# OvenController.net
KiCad netlist of a schematic drawn in EAGLE
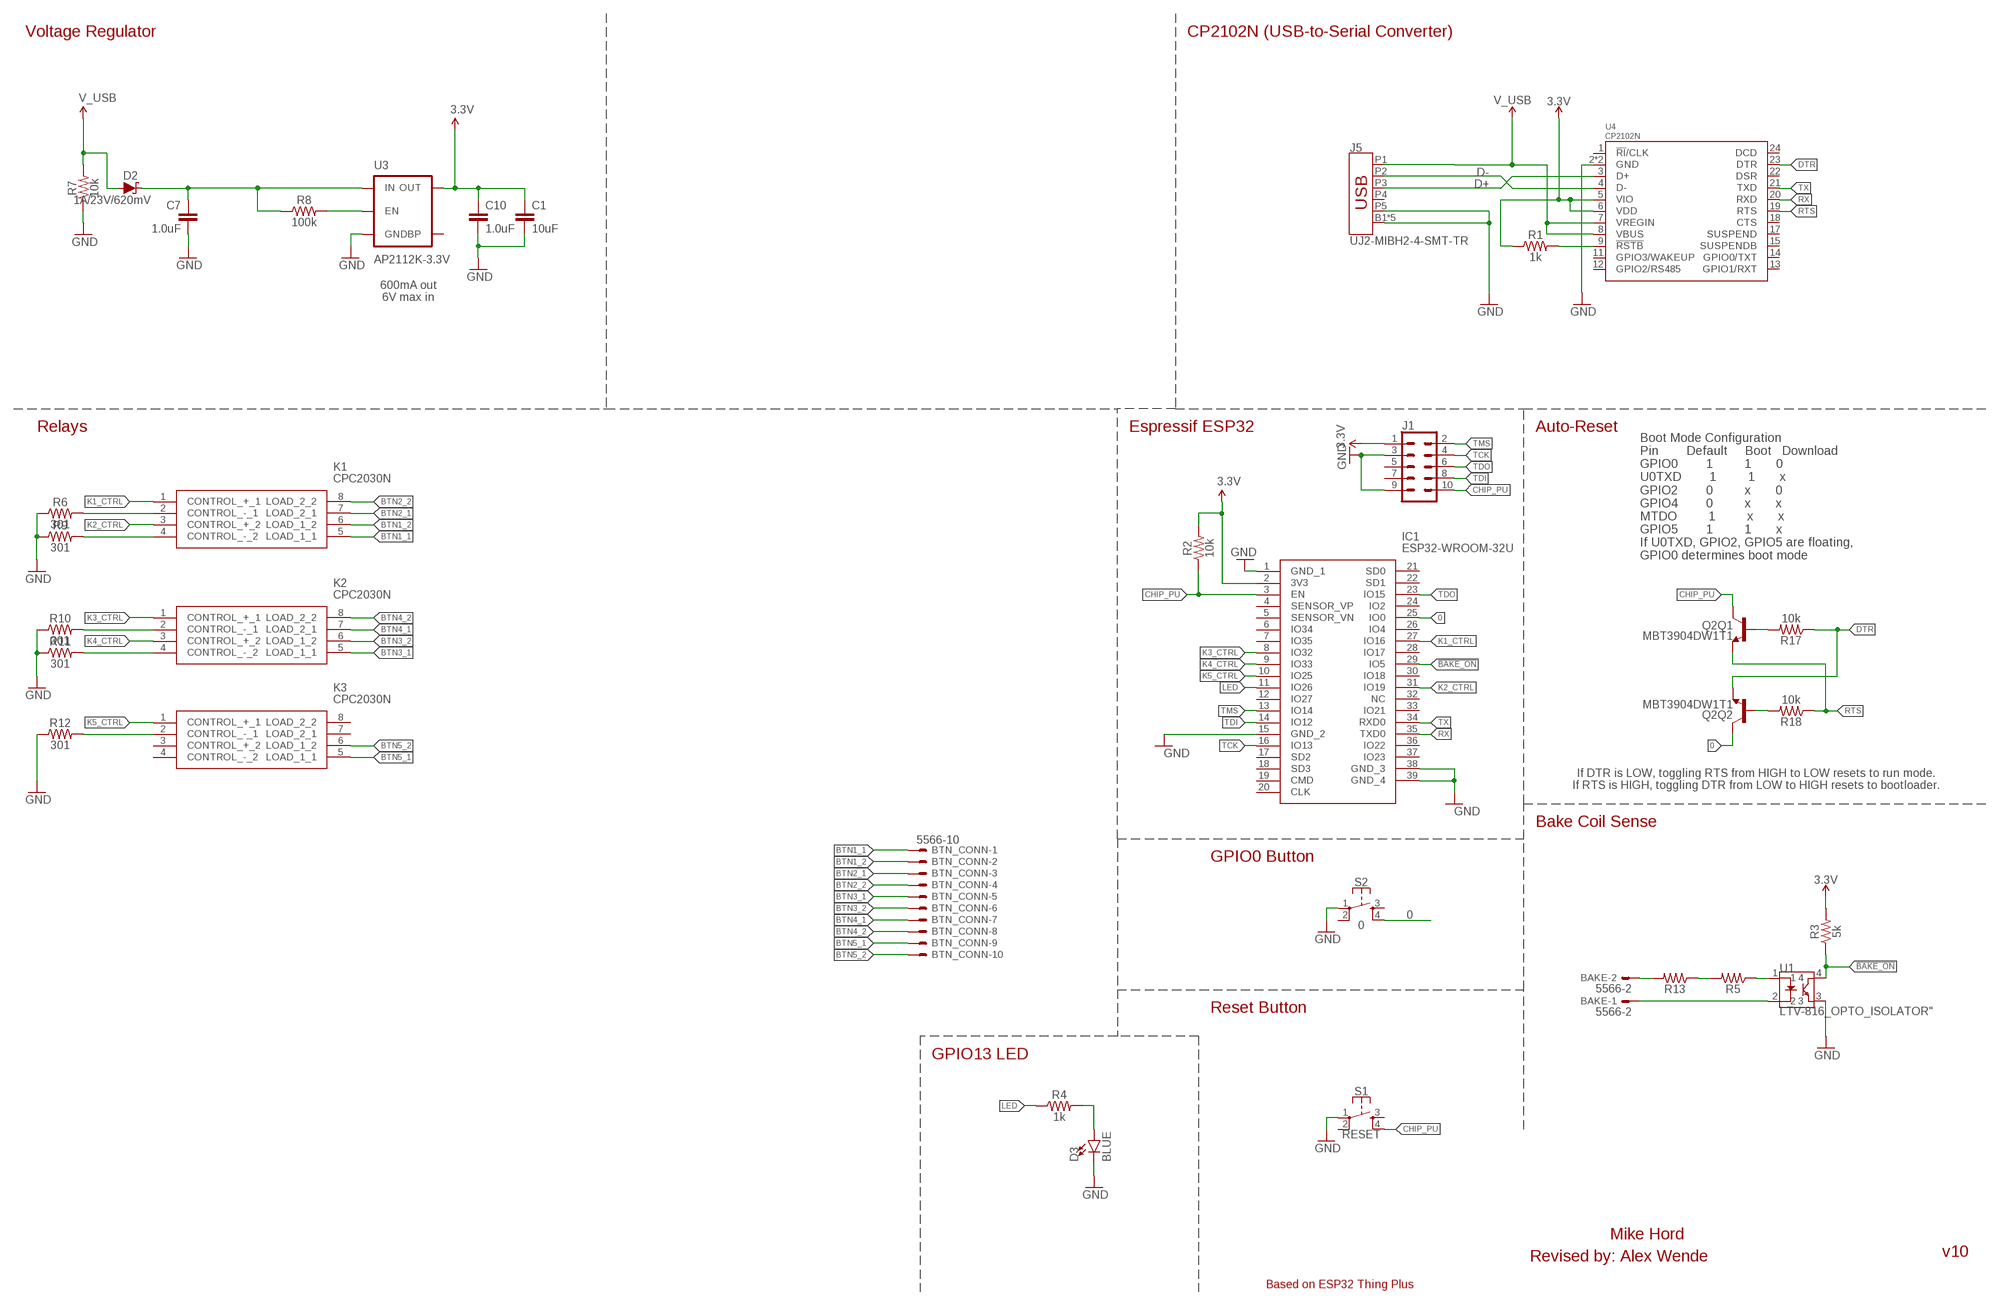
[diagram p0: schematic, sheet 1]

(export (version "E")
  (design (tool "Eeschema 10.0.6"))
  (components
    (comp (ref "BAKE")
      (value "5566-2")
      (footprint "eagle-import:5566-2")
      (fields (field (name "MF") "MOLEX"))
      (libsource (lib "eagle-import") (part "5566-2"))
    )
    (comp (ref "BTN_CONN")
      (value "5566-10")
      (footprint "eagle-import:5566-10")
      (fields (field (name "MF") "MOLEX"))
      (libsource (lib "eagle-import") (part "5566-10"))
    )
    (comp (ref "C1")
      (value "10uF")
      (footprint "eagle-import:0603")
      (libsource (lib "eagle-import") (part "10UF-0603-6.3V-20%"))
    )
    (comp (ref "C7")
      (value "1.0uF")
      (footprint "eagle-import:0603")
      (libsource (lib "eagle-import") (part "1.0UF-0603-16V-10%-X7R"))
    )
    (comp (ref "C10")
      (value "1.0uF")
      (footprint "eagle-import:0603")
      (libsource (lib "eagle-import") (part "1.0UF-0603-16V-10%-X7R"))
    )
    (comp (ref "D2")
      (value "1A/23V/620mV")
      (footprint "eagle-import:SOD-323")
      (libsource (lib "eagle-import") (part "DIODE-SCHOTTKY-BAT20J"))
    )
    (comp (ref "D3")
      (value "BLUE")
      (footprint "eagle-import:LED-0603")
      (libsource (lib "eagle-import") (part "LED-BLUE0603"))
    )
    (comp (ref "IC1")
      (value "ESP32-WROOM-32U")
      (footprint "eagle-import:ESP32WROOM32D")
      (fields (field (name "MOUSER_PART_NUMBER") "356-ESP32-WROOM-32U"))
      (libsource (lib "eagle-import") (part "ESP32-WROOM-32U"))
    )
    (comp (ref "J1")
      (value "CONN_05X2PTH")
      (footprint "eagle-import:2X5")
      (libsource (lib "eagle-import") (part "CONN_05X2PTH"))
    )
    (comp (ref "J5")
      (value "UJ2-MIBH2-4-SMT-TR")
      (footprint "eagle-import:UJ2-MIBH2-4-SMT-TR")
      (fields (field (name "MFR") "CUI"))
      (libsource (lib "eagle-import") (part "UJ2-MIBH2-4-SMT-TR"))
    )
    (comp (ref "K1")
      (value "CPC2030N")
      (footprint "eagle-import:SOP254P610X218-8N")
      (fields (field (name "MOUSER_PART_NUMBER") "849-CPC2030N"))
      (libsource (lib "eagle-import") (part "CPC2030N"))
    )
    (comp (ref "K2")
      (value "CPC2030N")
      (footprint "eagle-import:SOP254P610X218-8N")
      (fields (field (name "MOUSER_PART_NUMBER") "849-CPC2030N"))
      (libsource (lib "eagle-import") (part "CPC2030N"))
    )
    (comp (ref "K3")
      (value "CPC2030N")
      (footprint "eagle-import:SOP254P610X218-8N")
      (fields (field (name "MOUSER_PART_NUMBER") "849-CPC2030N"))
      (libsource (lib "eagle-import") (part "CPC2030N"))
    )
    (comp (ref "Q2")
      (value "MBT3904DW1T1")
      (footprint "eagle-import:SC70-6")
      (libsource (lib "eagle-import") (part "TRANS_NPN_DUAL-MBT3904DW1T1"))
    )
    (comp (ref "R1")
      (value "1k")
      (footprint "eagle-import:0603")
      (libsource (lib "eagle-import") (part "1KOHM-0603-1/10W-1%"))
    )
    (comp (ref "R2")
      (value "10k")
      (footprint "eagle-import:0603")
      (libsource (lib "eagle-import") (part "10KOHM-0603-1/10W-1%"))
    )
    (comp (ref "R3")
      (value "5k")
      (footprint "eagle-import:0603")
      (libsource (lib "eagle-import") (part "RESISTOR0603"))
    )
    (comp (ref "R4")
      (value "1k")
      (footprint "eagle-import:0603")
      (libsource (lib "eagle-import") (part "1KOHM-0603-1/10W-1%"))
    )
    (comp (ref "R5")
      (value "300")
      (footprint "eagle-import:R1210W")
      (libsource (lib "eagle-import") (part "R-US_R1210W"))
    )
    (comp (ref "R6")
      (value "301")
      (footprint "eagle-import:0603")
      (libsource (lib "eagle-import") (part "RESISTOR0603"))
    )
    (comp (ref "R7")
      (value "10k")
      (footprint "eagle-import:0603")
      (libsource (lib "eagle-import") (part "10KOHM-0603-1/10W-1%"))
    )
    (comp (ref "R8")
      (value "100k")
      (footprint "eagle-import:0603")
      (libsource (lib "eagle-import") (part "100KOHM-0603-1/10W-1%"))
    )
    (comp (ref "R9")
      (value "301")
      (footprint "eagle-import:0603")
      (libsource (lib "eagle-import") (part "RESISTOR0603"))
    )
    (comp (ref "R10")
      (value "301")
      (footprint "eagle-import:0603")
      (libsource (lib "eagle-import") (part "RESISTOR0603"))
    )
    (comp (ref "R11")
      (value "301")
      (footprint "eagle-import:0603")
      (libsource (lib "eagle-import") (part "RESISTOR0603"))
    )
    (comp (ref "R12")
      (value "301")
      (footprint "eagle-import:0603")
      (libsource (lib "eagle-import") (part "RESISTOR0603"))
    )
    (comp (ref "R13")
      (value "300")
      (footprint "eagle-import:R1210W")
      (libsource (lib "eagle-import") (part "R-US_R1210W"))
    )
    (comp (ref "R17")
      (value "10k")
      (footprint "eagle-import:0603")
      (libsource (lib "eagle-import") (part "10KOHM-0603-1/10W-1%"))
    )
    (comp (ref "R18")
      (value "10k")
      (footprint "eagle-import:0603")
      (libsource (lib "eagle-import") (part "10KOHM-0603-1/10W-1%"))
    )
    (comp (ref "S1")
      (value "RESET")
      (footprint "eagle-import:TACTILE_SWITCH_SMD_4.6X2.8MM")
      (libsource (lib "eagle-import") (part "MOMENTARY-SWITCH-SPST-2-SMD-4.6X2.8MM"))
    )
    (comp (ref "S2")
      (value "0")
      (footprint "eagle-import:TACTILE_SWITCH_SMD_4.6X2.8MM")
      (libsource (lib "eagle-import") (part "MOMENTARY-SWITCH-SPST-2-SMD-4.6X2.8MM"))
    )
    (comp (ref "U1")
      (value "LTV-816_OPTO_ISOLATOR\"")
      (footprint "eagle-import:LTV-816_4PIN_DIP")
      (libsource (lib "eagle-import") (part "LTV-816_OPTO_ISOLATOR{dblquote}"))
    )
    (comp (ref "U3")
      (value "AP2112K-3.3V")
      (footprint "eagle-import:SOT23-5")
      (libsource (lib "eagle-import") (part "V_REG_LDOSMD"))
    )
    (comp (ref "U4")
      (value "CP2102N")
      (footprint "eagle-import:QFN24")
      (libsource (lib "eagle-import") (part "CP2102N"))
    )
  )
  (nets
    (net (code "1") (name "/CONTROL_+_2") (class "Default")
      (node (ref "K3") (pin "3") (pinfunction "CONTROL_+_2_3") (pintype "power_in"))
    )
    (net (code "2") (name "/CONTROL_-_2") (class "Default")
      (node (ref "K3") (pin "4") (pinfunction "CONTROL_-_2_4") (pintype "power_in"))
    )
    (net (code "3") (name "/D+") (class "Default")
      (node (ref "J5") (pin "P3") (pinfunction "D+_P3") (pintype "bidirectional"))
      (node (ref "U4") (pin "3") (pinfunction "D+_3") (pintype "bidirectional"))
    )
    (net (code "4") (name "/D-") (class "Default")
      (node (ref "J5") (pin "P2") (pinfunction "D-_P2") (pintype "bidirectional"))
      (node (ref "U4") (pin "4") (pinfunction "D-_4") (pintype "bidirectional"))
    )
    (net (code "5") (name "/~{BAKE_ON}") (class "Default")
      (node (ref "IC1") (pin "29") (pinfunction "IO5_29") (pintype "bidirectional"))
      (node (ref "R3") (pin "1") (pinfunction "1_1") (pintype "passive"))
      (node (ref "U1") (pin "4") (pinfunction "4_4") (pintype "bidirectional"))
    )
    (net (code "6") (name "0") (class "Default")
      (node (ref "IC1") (pin "25") (pinfunction "IO0_25") (pintype "bidirectional"))
      (node (ref "Q2") (pin "6") (pinfunction "C_6") (pintype "passive"))
      (node (ref "S2") (pin "4") (pinfunction "4_4") (pintype "passive"))
    )
    (net (code "7") (name "3.3V") (class "Default")
      (node (ref "C1") (pin "1") (pinfunction "1_1") (pintype "passive"))
      (node (ref "C10") (pin "1") (pinfunction "1_1") (pintype "passive"))
      (node (ref "IC1") (pin "2") (pinfunction "3V3_2") (pintype "bidirectional"))
      (node (ref "J1") (pin "1") (pinfunction "1_1") (pintype "passive"))
      (node (ref "R1") (pin "1") (pinfunction "1_1") (pintype "passive"))
      (node (ref "R2") (pin "2") (pinfunction "2_2") (pintype "passive"))
      (node (ref "R3") (pin "2") (pinfunction "2_2") (pintype "passive"))
      (node (ref "U3") (pin "5") (pinfunction "OUT_5") (pintype "passive"))
      (node (ref "U4") (pin "5") (pinfunction "VIO_5") (pintype "bidirectional"))
      (node (ref "U4") (pin "6") (pinfunction "VDD_6") (pintype "bidirectional"))
    )
    (net (code "8") (name "BTN1_1") (class "Default")
      (node (ref "BTN_CONN") (pin "1") (pinfunction "S_1") (pintype "passive"))
      (node (ref "K1") (pin "5") (pinfunction "LOAD_1_1_5") (pintype "bidirectional"))
    )
    (net (code "9") (name "BTN1_2") (class "Default")
      (node (ref "BTN_CONN") (pin "2") (pinfunction "S_2") (pintype "passive"))
      (node (ref "K1") (pin "6") (pinfunction "LOAD_1_2_6") (pintype "bidirectional"))
    )
    (net (code "10") (name "BTN2_1") (class "Default")
      (node (ref "BTN_CONN") (pin "3") (pinfunction "S_3") (pintype "passive"))
      (node (ref "K1") (pin "7") (pinfunction "LOAD_2_1_7") (pintype "bidirectional"))
    )
    (net (code "11") (name "BTN2_2") (class "Default")
      (node (ref "BTN_CONN") (pin "4") (pinfunction "S_4") (pintype "passive"))
      (node (ref "K1") (pin "8") (pinfunction "LOAD_2_2_8") (pintype "bidirectional"))
    )
    (net (code "12") (name "BTN3_1") (class "Default")
      (node (ref "BTN_CONN") (pin "5") (pinfunction "S_5") (pintype "passive"))
      (node (ref "K2") (pin "5") (pinfunction "LOAD_1_1_5") (pintype "bidirectional"))
    )
    (net (code "13") (name "BTN3_2") (class "Default")
      (node (ref "BTN_CONN") (pin "6") (pinfunction "S_6") (pintype "passive"))
      (node (ref "K2") (pin "6") (pinfunction "LOAD_1_2_6") (pintype "bidirectional"))
    )
    (net (code "14") (name "BTN4_1") (class "Default")
      (node (ref "BTN_CONN") (pin "7") (pinfunction "S_7") (pintype "passive"))
      (node (ref "K2") (pin "7") (pinfunction "LOAD_2_1_7") (pintype "bidirectional"))
    )
    (net (code "15") (name "BTN4_2") (class "Default")
      (node (ref "BTN_CONN") (pin "8") (pinfunction "S_8") (pintype "passive"))
      (node (ref "K2") (pin "8") (pinfunction "LOAD_2_2_8") (pintype "bidirectional"))
    )
    (net (code "16") (name "BTN5_1") (class "Default")
      (node (ref "BTN_CONN") (pin "9") (pinfunction "S_9") (pintype "passive"))
      (node (ref "K3") (pin "5") (pinfunction "LOAD_1_1_5") (pintype "bidirectional"))
    )
    (net (code "17") (name "BTN5_2") (class "Default")
      (node (ref "BTN_CONN") (pin "10") (pinfunction "S_10") (pintype "passive"))
      (node (ref "K3") (pin "6") (pinfunction "LOAD_1_2_6") (pintype "bidirectional"))
    )
    (net (code "18") (name "CHIP_PU") (class "Default")
      (node (ref "IC1") (pin "3") (pinfunction "EN_3") (pintype "bidirectional"))
      (node (ref "J1") (pin "10") (pinfunction "10_10") (pintype "passive"))
      (node (ref "Q2") (pin "3") (pinfunction "C_3") (pintype "passive"))
      (node (ref "R2") (pin "1") (pinfunction "1_1") (pintype "passive"))
      (node (ref "S1") (pin "4") (pinfunction "4_4") (pintype "passive"))
    )
    (net (code "19") (name "DTR") (class "Default")
      (node (ref "Q2") (pin "1") (pinfunction "E_1") (pintype "passive"))
      (node (ref "R17") (pin "1") (pinfunction "1_1") (pintype "passive"))
      (node (ref "U4") (pin "23") (pinfunction "DTR_23") (pintype "bidirectional"))
    )
    (net (code "20") (name "GND") (class "Default")
      (node (ref "C1") (pin "2") (pinfunction "2_2") (pintype "passive"))
      (node (ref "C10") (pin "2") (pinfunction "2_2") (pintype "passive"))
      (node (ref "C7") (pin "2") (pinfunction "2_2") (pintype "passive"))
      (node (ref "D3") (pin "C") (pinfunction "C_C") (pintype "passive"))
      (node (ref "IC1") (pin "1") (pinfunction "GND_1_1") (pintype "bidirectional"))
      (node (ref "IC1") (pin "15") (pinfunction "GND_2_15") (pintype "bidirectional"))
      (node (ref "IC1") (pin "38") (pinfunction "GND_3_38") (pintype "bidirectional"))
      (node (ref "IC1") (pin "39") (pinfunction "GND_4_39") (pintype "bidirectional"))
      (node (ref "J1") (pin "3") (pinfunction "3_3") (pintype "passive"))
      (node (ref "J1") (pin "9") (pinfunction "9_9") (pintype "passive"))
      (node (ref "J5") (pin "B1") (pinfunction "SHIELD_B1") (pintype "bidirectional"))
      (node (ref "J5") (pin "B2") (pinfunction "SHIELD_B2") (pintype "bidirectional"))
      (node (ref "J5") (pin "B3") (pinfunction "SHIELD_B3") (pintype "bidirectional"))
      (node (ref "J5") (pin "B4") (pinfunction "SHIELD_B4") (pintype "bidirectional"))
      (node (ref "J5") (pin "B5") (pinfunction "SHIELD_B5") (pintype "bidirectional"))
      (node (ref "J5") (pin "P5") (pinfunction "GND_P5") (pintype "power_in"))
      (node (ref "R10") (pin "1") (pinfunction "1_1") (pintype "passive"))
      (node (ref "R11") (pin "1") (pinfunction "1_1") (pintype "passive"))
      (node (ref "R12") (pin "1") (pinfunction "1_1") (pintype "passive"))
      (node (ref "R6") (pin "1") (pinfunction "1_1") (pintype "passive"))
      (node (ref "R7") (pin "1") (pinfunction "1_1") (pintype "passive"))
      (node (ref "R9") (pin "1") (pinfunction "1_1") (pintype "passive"))
      (node (ref "S1") (pin "1") (pinfunction "1_1") (pintype "passive"))
      (node (ref "S2") (pin "1") (pinfunction "1_1") (pintype "passive"))
      (node (ref "U1") (pin "3") (pinfunction "3_3") (pintype "bidirectional"))
      (node (ref "U3") (pin "2") (pinfunction "GND_2") (pintype "input"))
      (node (ref "U4") (pin "2") (pinfunction "GND_2") (pintype "bidirectional"))
      (node (ref "U4") (pin "PAD") (pinfunction "GND_PAD") (pintype "bidirectional"))
    )
    (net (code "21") (name "K1_CTRL") (class "Default")
      (node (ref "IC1") (pin "27") (pinfunction "IO16_27") (pintype "bidirectional"))
      (node (ref "K1") (pin "1") (pinfunction "CONTROL_+_1_1") (pintype "power_in"))
    )
    (net (code "22") (name "K2_CTRL") (class "Default")
      (node (ref "IC1") (pin "31") (pinfunction "IO19_31") (pintype "bidirectional"))
      (node (ref "K1") (pin "3") (pinfunction "CONTROL_+_2_3") (pintype "power_in"))
    )
    (net (code "23") (name "K3_CTRL") (class "Default")
      (node (ref "IC1") (pin "8") (pinfunction "IO32_8") (pintype "bidirectional"))
      (node (ref "K2") (pin "1") (pinfunction "CONTROL_+_1_1") (pintype "power_in"))
    )
    (net (code "24") (name "K4_CTRL") (class "Default")
      (node (ref "IC1") (pin "9") (pinfunction "IO33_9") (pintype "bidirectional"))
      (node (ref "K2") (pin "3") (pinfunction "CONTROL_+_2_3") (pintype "power_in"))
    )
    (net (code "25") (name "K5_CTRL") (class "Default")
      (node (ref "IC1") (pin "10") (pinfunction "IO25_10") (pintype "bidirectional"))
      (node (ref "K3") (pin "1") (pinfunction "CONTROL_+_1_1") (pintype "power_in"))
    )
    (net (code "26") (name "LED") (class "Default")
      (node (ref "IC1") (pin "11") (pinfunction "IO26_11") (pintype "bidirectional"))
      (node (ref "R4") (pin "1") (pinfunction "1_1") (pintype "passive"))
    )
    (net (code "27") (name "Net-(BAKEA-S)") (class "Default")
      (node (ref "BAKE") (pin "1") (pinfunction "S_1") (pintype "passive"))
      (node (ref "U1") (pin "2") (pinfunction "2_2") (pintype "bidirectional"))
    )
    (net (code "28") (name "Net-(BAKEB-S)") (class "Default")
      (node (ref "BAKE") (pin "2") (pinfunction "S_2") (pintype "passive"))
      (node (ref "R13") (pin "2") (pinfunction "2_2") (pintype "passive"))
    )
    (net (code "29") (name "Net-(D3-PadA)") (class "Default")
      (node (ref "D3") (pin "A") (pinfunction "A_A") (pintype "passive"))
      (node (ref "R4") (pin "2") (pinfunction "2_2") (pintype "passive"))
    )
    (net (code "30") (name "Net-(K1-CONTROL_-_1)") (class "Default")
      (node (ref "K1") (pin "2") (pinfunction "CONTROL_-_1_2") (pintype "power_in"))
      (node (ref "R6") (pin "2") (pinfunction "2_2") (pintype "passive"))
    )
    (net (code "31") (name "Net-(K1-CONTROL_-_2)") (class "Default")
      (node (ref "K1") (pin "4") (pinfunction "CONTROL_-_2_4") (pintype "power_in"))
      (node (ref "R9") (pin "2") (pinfunction "2_2") (pintype "passive"))
    )
    (net (code "32") (name "Net-(K2-CONTROL_-_1)") (class "Default")
      (node (ref "K2") (pin "2") (pinfunction "CONTROL_-_1_2") (pintype "power_in"))
      (node (ref "R10") (pin "2") (pinfunction "2_2") (pintype "passive"))
    )
    (net (code "33") (name "Net-(K2-CONTROL_-_2)") (class "Default")
      (node (ref "K2") (pin "4") (pinfunction "CONTROL_-_2_4") (pintype "power_in"))
      (node (ref "R11") (pin "2") (pinfunction "2_2") (pintype "passive"))
    )
    (net (code "34") (name "Net-(K3-CONTROL_-_1)") (class "Default")
      (node (ref "K3") (pin "2") (pinfunction "CONTROL_-_1_2") (pintype "power_in"))
      (node (ref "R12") (pin "2") (pinfunction "2_2") (pintype "passive"))
    )
    (net (code "35") (name "Net-(Q2A-B)") (class "Default")
      (node (ref "Q2") (pin "5") (pinfunction "B_5") (pintype "passive"))
      (node (ref "R17") (pin "2") (pinfunction "2_2") (pintype "passive"))
    )
    (net (code "36") (name "Net-(Q2B-B)") (class "Default")
      (node (ref "Q2") (pin "2") (pinfunction "B_2") (pintype "passive"))
      (node (ref "R18") (pin "2") (pinfunction "2_2") (pintype "passive"))
    )
    (net (code "37") (name "Net-(R5-Pad1)") (class "Default")
      (node (ref "R5") (pin "1") (pinfunction "1_1") (pintype "passive"))
      (node (ref "U1") (pin "1") (pinfunction "1_1") (pintype "bidirectional"))
    )
    (net (code "38") (name "Net-(R13-Pad1)") (class "Default")
      (node (ref "R13") (pin "1") (pinfunction "1_1") (pintype "passive"))
      (node (ref "R5") (pin "2") (pinfunction "2_2") (pintype "passive"))
    )
    (net (code "39") (name "Net-(U3-EN)") (class "Default")
      (node (ref "R8") (pin "2") (pinfunction "2_2") (pintype "passive"))
      (node (ref "U3") (pin "3") (pinfunction "EN_3") (pintype "input"))
    )
    (net (code "40") (name "Net-(U3-IN)") (class "Default")
      (node (ref "C7") (pin "1") (pinfunction "1_1") (pintype "passive"))
      (node (ref "D2") (pin "C") (pinfunction "C_C") (pintype "passive"))
      (node (ref "R8") (pin "1") (pinfunction "1_1") (pintype "passive"))
      (node (ref "U3") (pin "1") (pinfunction "IN_1") (pintype "input"))
    )
    (net (code "41") (name "Net-(U4-~{RSTB})") (class "Default")
      (node (ref "R1") (pin "2") (pinfunction "2_2") (pintype "passive"))
      (node (ref "U4") (pin "9") (pinfunction "~{RSTB}_9") (pintype "bidirectional"))
    )
    (net (code "42") (name "RTS") (class "Default")
      (node (ref "Q2") (pin "4") (pinfunction "E_4") (pintype "passive"))
      (node (ref "R18") (pin "1") (pinfunction "1_1") (pintype "passive"))
      (node (ref "U4") (pin "19") (pinfunction "RTS_19") (pintype "bidirectional"))
    )
    (net (code "43") (name "RX") (class "Default")
      (node (ref "IC1") (pin "35") (pinfunction "TXD0_35") (pintype "bidirectional"))
      (node (ref "U4") (pin "20") (pinfunction "RXD_20") (pintype "bidirectional"))
    )
    (net (code "44") (name "TCK") (class "Default")
      (node (ref "IC1") (pin "16") (pinfunction "IO13_16") (pintype "bidirectional"))
      (node (ref "J1") (pin "4") (pinfunction "4_4") (pintype "passive"))
    )
    (net (code "45") (name "TDI") (class "Default")
      (node (ref "IC1") (pin "14") (pinfunction "IO12_14") (pintype "bidirectional"))
      (node (ref "J1") (pin "8") (pinfunction "8_8") (pintype "passive"))
    )
    (net (code "46") (name "TDO") (class "Default")
      (node (ref "IC1") (pin "23") (pinfunction "IO15_23") (pintype "bidirectional"))
      (node (ref "J1") (pin "6") (pinfunction "6_6") (pintype "passive"))
    )
    (net (code "47") (name "TMS") (class "Default")
      (node (ref "IC1") (pin "13") (pinfunction "IO14_13") (pintype "bidirectional"))
      (node (ref "J1") (pin "2") (pinfunction "2_2") (pintype "passive"))
    )
    (net (code "48") (name "TX") (class "Default")
      (node (ref "IC1") (pin "34") (pinfunction "RXD0_34") (pintype "bidirectional"))
      (node (ref "U4") (pin "21") (pinfunction "TXD_21") (pintype "bidirectional"))
    )
    (net (code "49") (name "V_USB") (class "Default")
      (node (ref "D2") (pin "A") (pinfunction "A_A") (pintype "passive"))
      (node (ref "J5") (pin "P1") (pinfunction "VBUS_P1") (pintype "power_in"))
      (node (ref "R7") (pin "2") (pinfunction "2_2") (pintype "passive"))
      (node (ref "U4") (pin "7") (pinfunction "VREGIN_7") (pintype "bidirectional"))
      (node (ref "U4") (pin "8") (pinfunction "VBUS_8") (pintype "bidirectional"))
    )
    (net (code "50") (name "unconnected-(IC1-CLK-Pad20)") (class "Default")
      (node (ref "IC1") (pin "20") (pinfunction "CLK_20") (pintype "bidirectional"))
    )
    (net (code "51") (name "unconnected-(IC1-CMD-Pad19)") (class "Default")
      (node (ref "IC1") (pin "19") (pinfunction "CMD_19") (pintype "bidirectional"))
    )
    (net (code "52") (name "unconnected-(IC1-IO2-Pad24)") (class "Default")
      (node (ref "IC1") (pin "24") (pinfunction "IO2_24") (pintype "bidirectional"))
    )
    (net (code "53") (name "unconnected-(IC1-IO4-Pad26)") (class "Default")
      (node (ref "IC1") (pin "26") (pinfunction "IO4_26") (pintype "bidirectional"))
    )
    (net (code "54") (name "unconnected-(IC1-IO17-Pad28)") (class "Default")
      (node (ref "IC1") (pin "28") (pinfunction "IO17_28") (pintype "bidirectional"))
    )
    (net (code "55") (name "unconnected-(IC1-IO18-Pad30)") (class "Default")
      (node (ref "IC1") (pin "30") (pinfunction "IO18_30") (pintype "bidirectional"))
    )
    (net (code "56") (name "unconnected-(IC1-IO21-Pad33)") (class "Default")
      (node (ref "IC1") (pin "33") (pinfunction "IO21_33") (pintype "bidirectional"))
    )
    (net (code "57") (name "unconnected-(IC1-IO22-Pad36)") (class "Default")
      (node (ref "IC1") (pin "36") (pinfunction "IO22_36") (pintype "bidirectional"))
    )
    (net (code "58") (name "unconnected-(IC1-IO23-Pad37)") (class "Default")
      (node (ref "IC1") (pin "37") (pinfunction "IO23_37") (pintype "bidirectional"))
    )
    (net (code "59") (name "unconnected-(IC1-IO27-Pad12)") (class "Default")
      (node (ref "IC1") (pin "12") (pinfunction "IO27_12") (pintype "bidirectional"))
    )
    (net (code "60") (name "unconnected-(IC1-IO34-Pad6)") (class "Default")
      (node (ref "IC1") (pin "6") (pinfunction "IO34_6") (pintype "bidirectional"))
    )
    (net (code "61") (name "unconnected-(IC1-IO35-Pad7)") (class "Default")
      (node (ref "IC1") (pin "7") (pinfunction "IO35_7") (pintype "bidirectional"))
    )
    (net (code "62") (name "unconnected-(IC1-NC-Pad32)") (class "Default")
      (node (ref "IC1") (pin "32") (pinfunction "NC_32") (pintype "no_connect"))
    )
    (net (code "63") (name "unconnected-(IC1-SD0-Pad21)") (class "Default")
      (node (ref "IC1") (pin "21") (pinfunction "SD0_21") (pintype "bidirectional"))
    )
    (net (code "64") (name "unconnected-(IC1-SD1-Pad22)") (class "Default")
      (node (ref "IC1") (pin "22") (pinfunction "SD1_22") (pintype "bidirectional"))
    )
    (net (code "65") (name "unconnected-(IC1-SD2-Pad17)") (class "Default")
      (node (ref "IC1") (pin "17") (pinfunction "SD2_17") (pintype "bidirectional"))
    )
    (net (code "66") (name "unconnected-(IC1-SD3-Pad18)") (class "Default")
      (node (ref "IC1") (pin "18") (pinfunction "SD3_18") (pintype "bidirectional"))
    )
    (net (code "67") (name "unconnected-(IC1-SENSOR_VN-Pad5)") (class "Default")
      (node (ref "IC1") (pin "5") (pinfunction "SENSOR_VN_5") (pintype "bidirectional"))
    )
    (net (code "68") (name "unconnected-(IC1-SENSOR_VP-Pad4)") (class "Default")
      (node (ref "IC1") (pin "4") (pinfunction "SENSOR_VP_4") (pintype "bidirectional"))
    )
    (net (code "69") (name "unconnected-(J1-Pad5)") (class "Default")
      (node (ref "J1") (pin "5") (pinfunction "5_5") (pintype "passive"))
    )
    (net (code "70") (name "unconnected-(J1-Pad7)") (class "Default")
      (node (ref "J1") (pin "7") (pinfunction "7_7") (pintype "passive"))
    )
    (net (code "71") (name "unconnected-(J5-ID-PadP4)") (class "Default")
      (node (ref "J5") (pin "P4") (pinfunction "ID_P4") (pintype "bidirectional"))
    )
    (net (code "72") (name "unconnected-(K3-LOAD_2_1-Pad7)") (class "Default")
      (node (ref "K3") (pin "7") (pinfunction "LOAD_2_1_7") (pintype "bidirectional"))
    )
    (net (code "73") (name "unconnected-(K3-LOAD_2_2-Pad8)") (class "Default")
      (node (ref "K3") (pin "8") (pinfunction "LOAD_2_2_8") (pintype "bidirectional"))
    )
    (net (code "74") (name "unconnected-(S1-Pad2)") (class "Default")
      (node (ref "S1") (pin "2") (pinfunction "2_2") (pintype "passive"))
    )
    (net (code "75") (name "unconnected-(S1-Pad3)") (class "Default")
      (node (ref "S1") (pin "3") (pinfunction "3_3") (pintype "passive"))
    )
    (net (code "76") (name "unconnected-(S2-Pad2)") (class "Default")
      (node (ref "S2") (pin "2") (pinfunction "2_2") (pintype "passive"))
    )
    (net (code "77") (name "unconnected-(S2-Pad3)") (class "Default")
      (node (ref "S2") (pin "3") (pinfunction "3_3") (pintype "passive"))
    )
    (net (code "78") (name "unconnected-(U3-BP-Pad4)") (class "Default")
      (node (ref "U3") (pin "4") (pinfunction "BP_4") (pintype "input"))
    )
    (net (code "79") (name "unconnected-(U4-CTS-Pad18)") (class "Default")
      (node (ref "U4") (pin "18") (pinfunction "CTS_18") (pintype "bidirectional"))
    )
    (net (code "80") (name "unconnected-(U4-DCD-Pad24)") (class "Default")
      (node (ref "U4") (pin "24") (pinfunction "DCD_24") (pintype "bidirectional"))
    )
    (net (code "81") (name "unconnected-(U4-DSR-Pad22)") (class "Default")
      (node (ref "U4") (pin "22") (pinfunction "DSR_22") (pintype "bidirectional"))
    )
    (net (code "82") (name "unconnected-(U4-GPIO0{slash}TXT-Pad14)") (class "Default")
      (node (ref "U4") (pin "14") (pinfunction "GPIO0/TXT_14") (pintype "bidirectional"))
    )
    (net (code "83") (name "unconnected-(U4-GPIO1{slash}RXT-Pad13)") (class "Default")
      (node (ref "U4") (pin "13") (pinfunction "GPIO1/RXT_13") (pintype "bidirectional"))
    )
    (net (code "84") (name "unconnected-(U4-GPIO2{slash}RS485-Pad12)") (class "Default")
      (node (ref "U4") (pin "12") (pinfunction "GPIO2/RS485_12") (pintype "bidirectional"))
    )
    (net (code "85") (name "unconnected-(U4-GPIO3{slash}WAKEUP-Pad11)") (class "Default")
      (node (ref "U4") (pin "11") (pinfunction "GPIO3/WAKEUP_11") (pintype "bidirectional"))
    )
    (net (code "86") (name "unconnected-(U4-SUSPEND-Pad17)") (class "Default")
      (node (ref "U4") (pin "17") (pinfunction "SUSPEND_17") (pintype "bidirectional"))
    )
    (net (code "87") (name "unconnected-(U4-SUSPENDB-Pad15)") (class "Default")
      (node (ref "U4") (pin "15") (pinfunction "SUSPENDB_15") (pintype "bidirectional"))
    )
    (net (code "88") (name "unconnected-(U4-~{RI}{slash}CLK-Pad1)") (class "Default")
      (node (ref "U4") (pin "1") (pinfunction "~{RI}/CLK_1") (pintype "bidirectional"))
    )
  )
)
